# IMX385_EVB_revA.net
KiCad netlist of a schematic drawn in Altium Designer
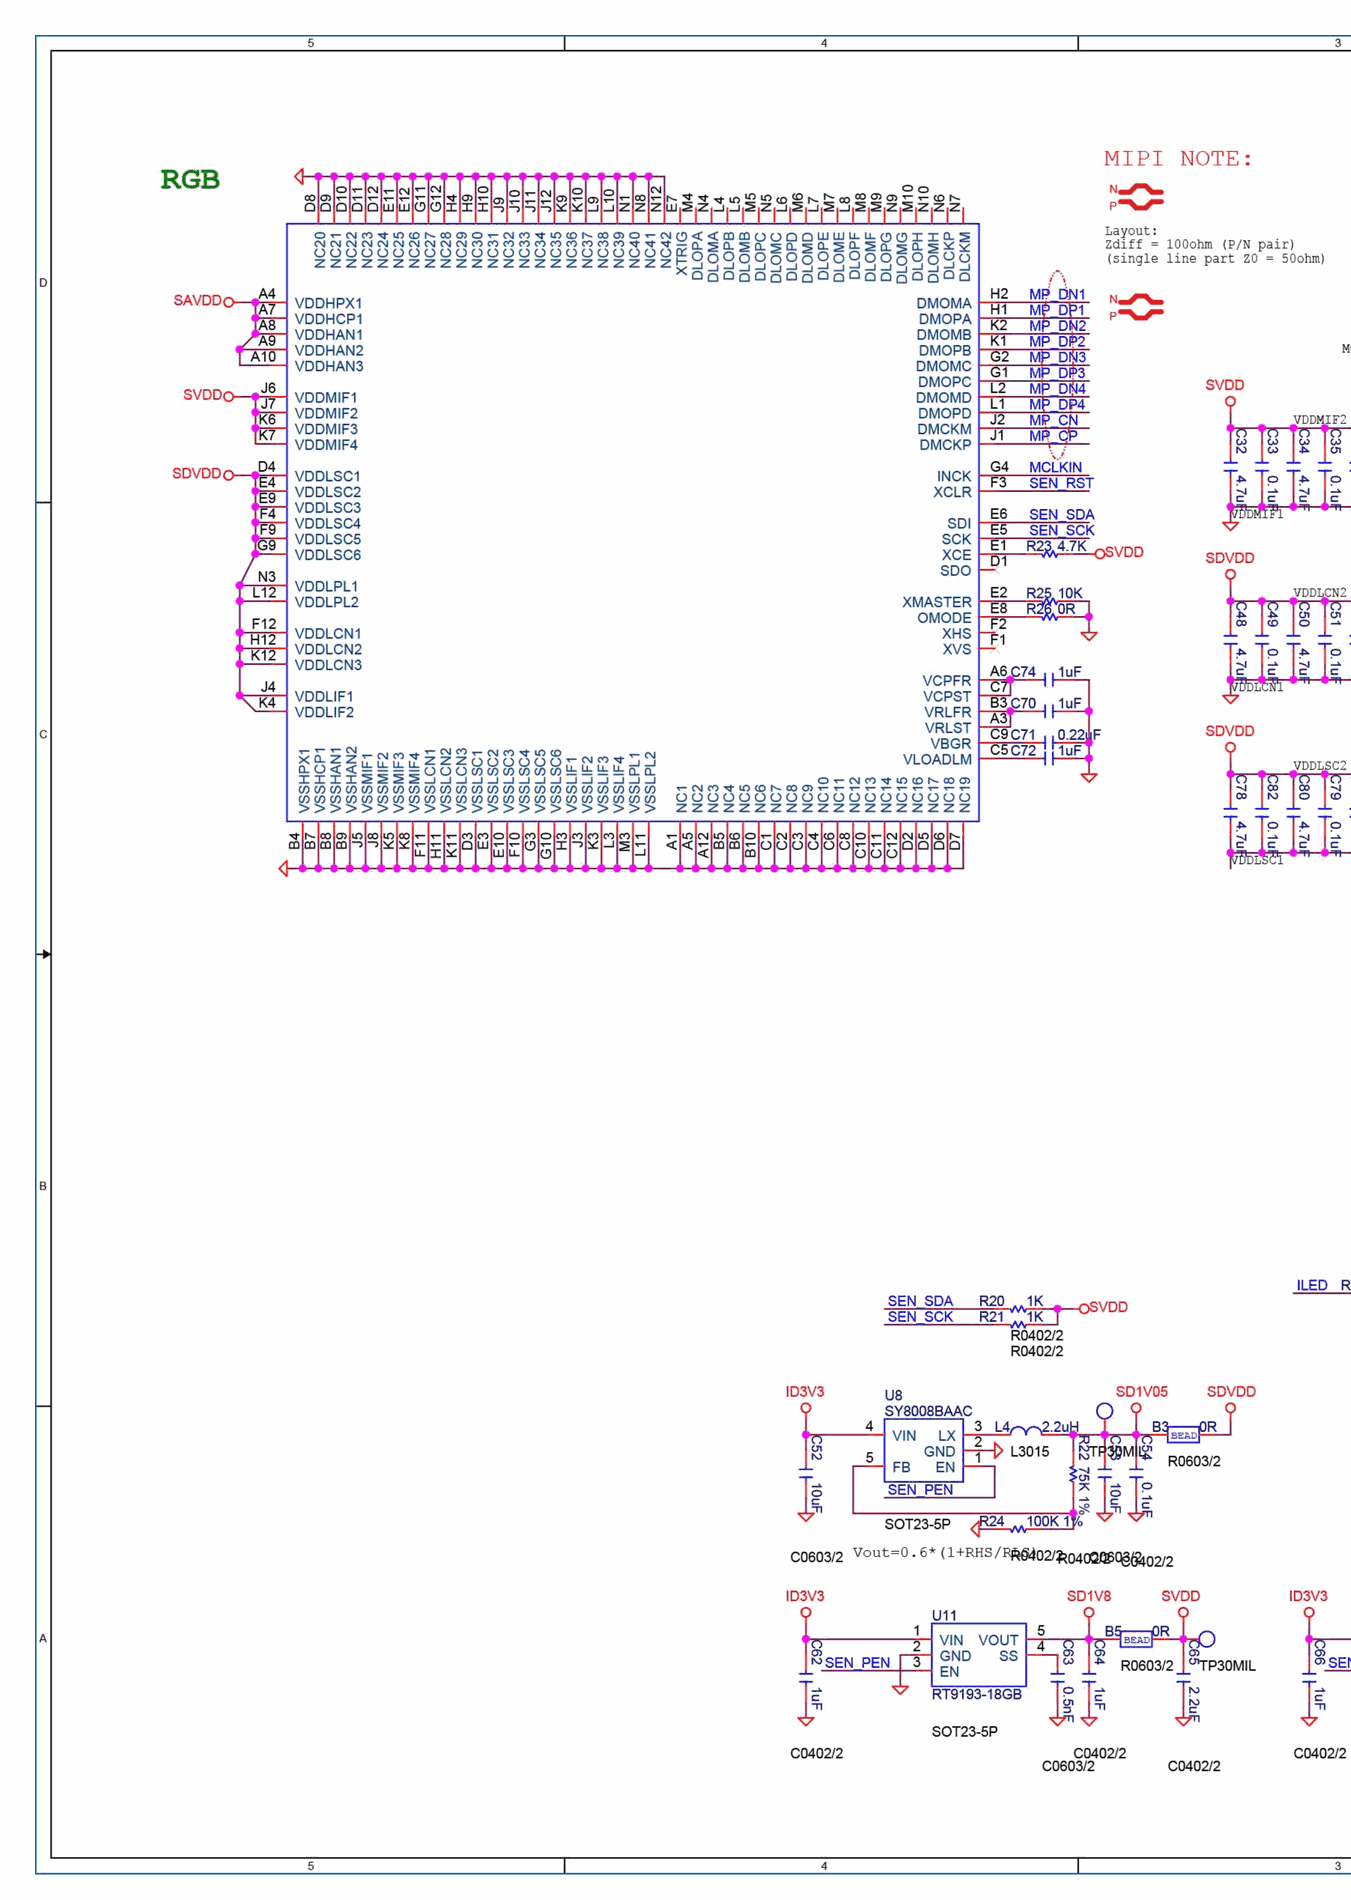
[diagram p0: IMX385_EVB_revA.SchDoc, top left]
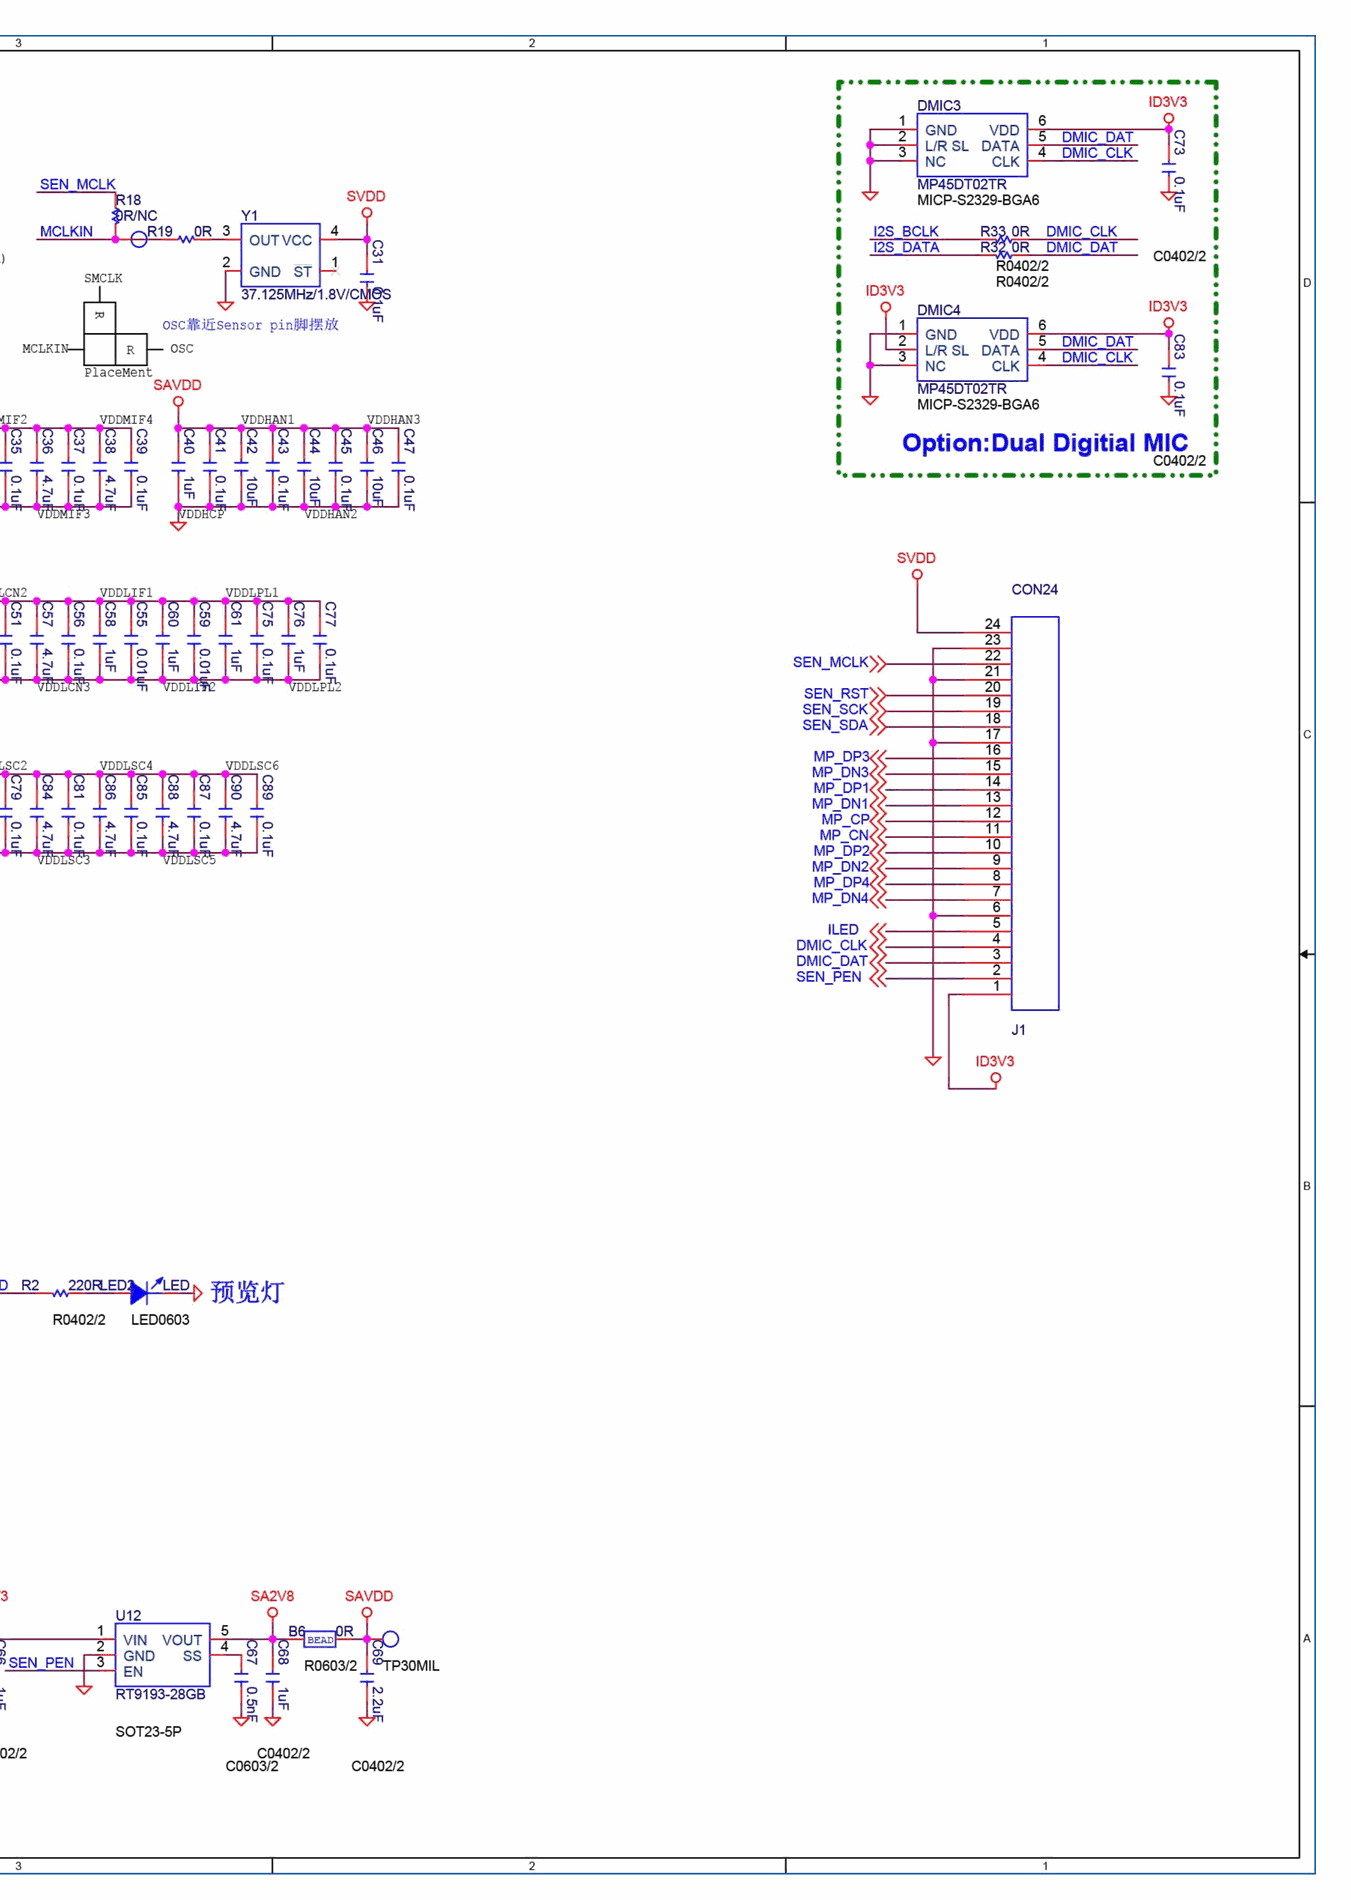
[diagram p1: IMX385_EVB_revA.SchDoc, top right]
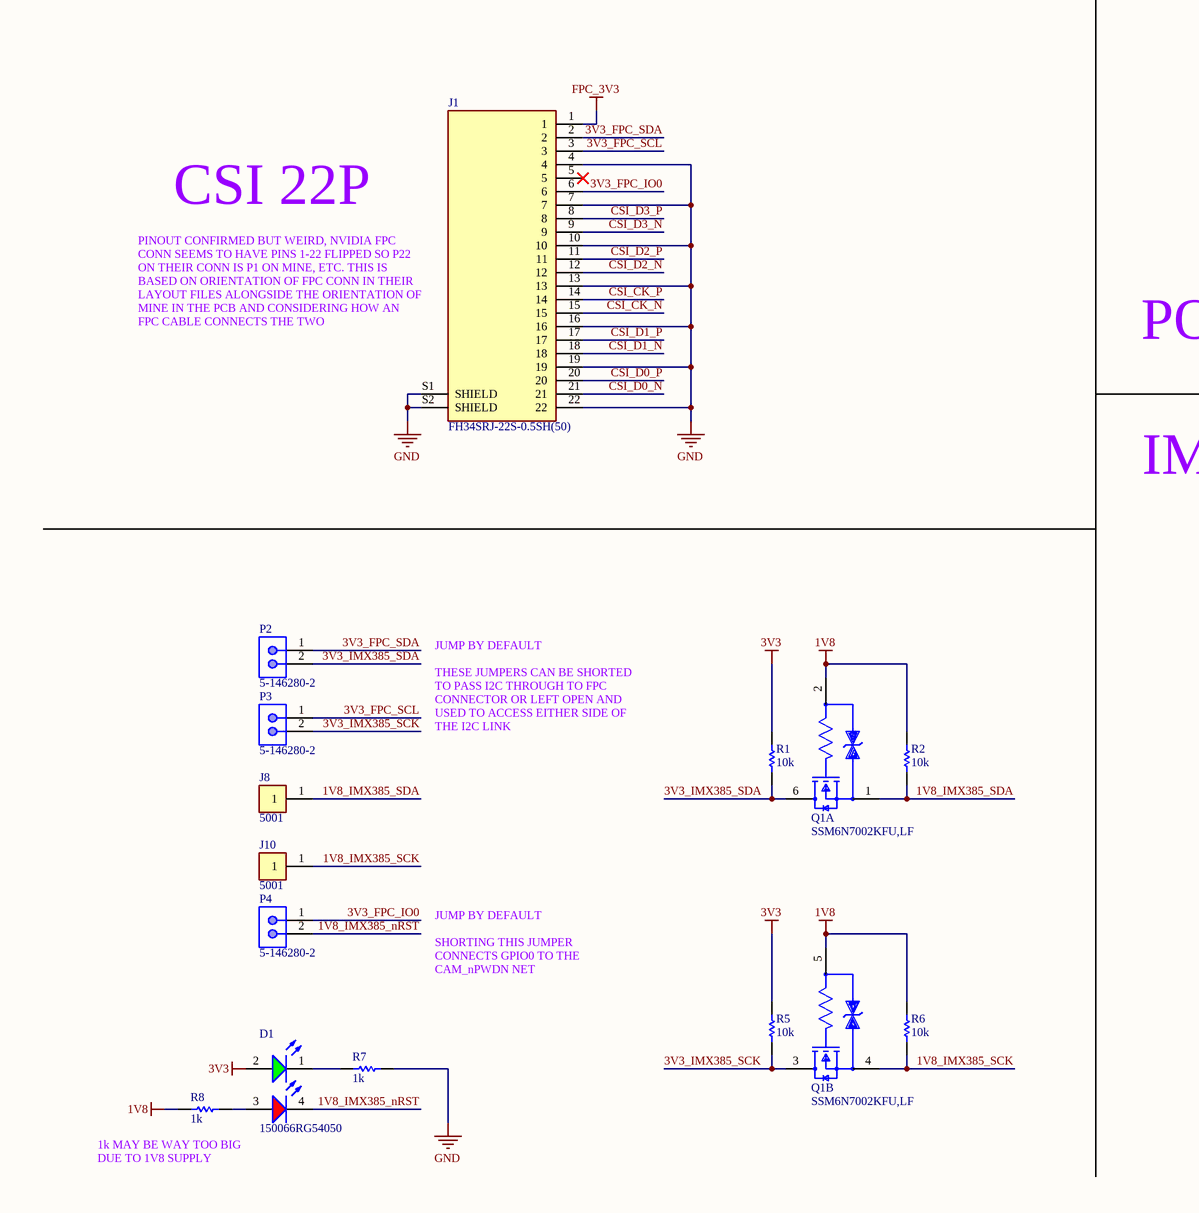
[diagram p2: IMX385_EVB_revA.SchDoc, bottom left]
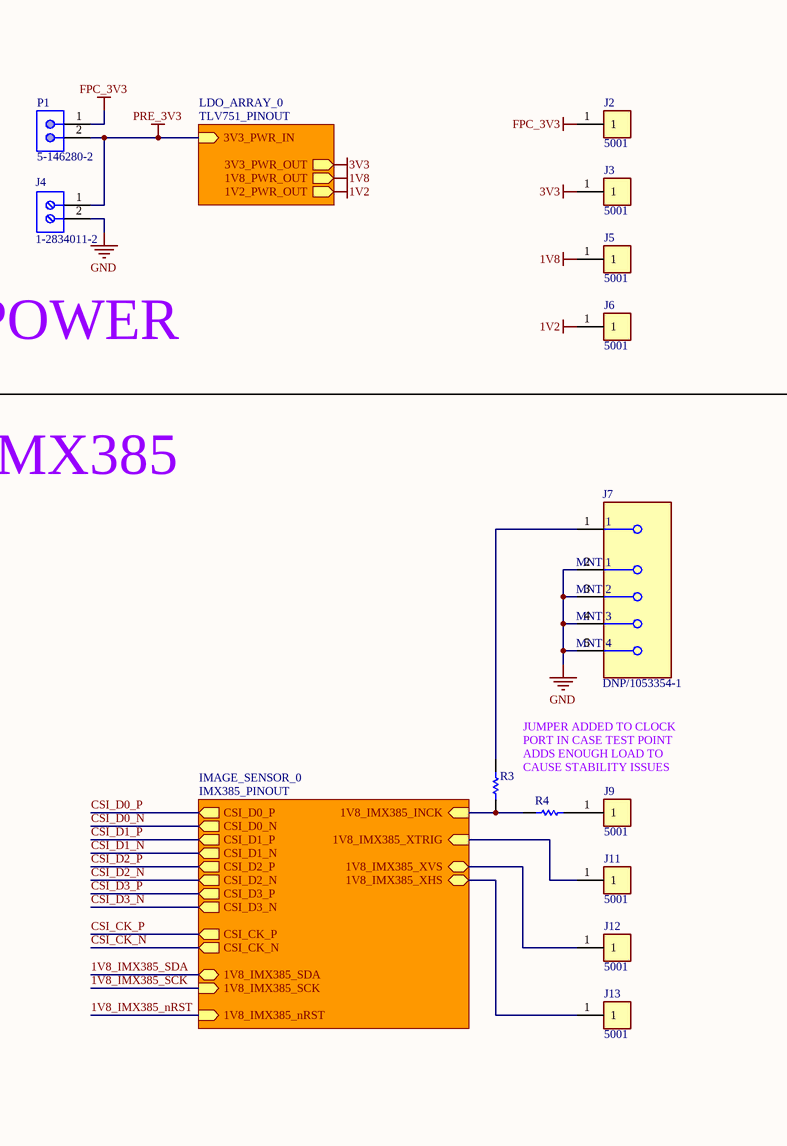
[diagram p3: IMX385_EVB_revA.SchDoc, bottom right]

(export (version "E")
  (design (tool "Eeschema 10.0.6"))
  (components
    (comp (ref "D1")
      (value "150066RG54050")
      (footprint "WL-SBCD_0606")
      (description "Led, Red/Grn, 180Mcd/230Mcd, 624Nm/525Nm Rohs Compliant: Yes")
      (fields (field (name "SOURCE") "rgled.SchLib"))
      (libsource (lib "Space Concordia") (part "CMP-004-00034-2"))
    )
    (comp (ref "J1")
      (value "FH34SRJ-22S-0.5SH(50)")
      (footprint "FH34SRJ-22S-0.5SH(50)-Footprint-1")
      (description "0.5Mm Pitch, 1.0Mm Height, Top And Bottom Contact, Back-Flip")
      (libsource (lib "Space Concordia") (part "FH34SRJ-22S-0.5SH(50)"))
    )
    (comp (ref "J2")
      (value "5001")
      (footprint "FP-5001-MFG")
      (description "PC TEST POINT MINIATURE BLACK")
      (libsource (lib "Altium Content Vault") (part "1e4615820a309e3ce90f9e6d957b7fa"))
    )
    (comp (ref "J3")
      (value "5001")
      (footprint "FP-5001-MFG")
      (description "PC TEST POINT MINIATURE BLACK")
      (libsource (lib "Altium Content Vault") (part "1e4615820a309e3ce90f9e6d957b7fa"))
    )
    (comp (ref "J4")
      (value "1-2834011-2")
      (footprint "1-2834011-2-Footprint-1")
      (description "Barrier Strip Terminal Block")
      (libsource (lib "Space Concordia") (part "1-2834011-2"))
    )
    (comp (ref "J5")
      (value "5001")
      (footprint "FP-5001-MFG")
      (description "PC TEST POINT MINIATURE BLACK")
      (libsource (lib "Altium Content Vault") (part "1e4615820a309e3ce90f9e6d957b7fa"))
    )
    (comp (ref "J6")
      (value "5001")
      (footprint "FP-5001-MFG")
      (description "PC TEST POINT MINIATURE BLACK")
      (libsource (lib "Altium Content Vault") (part "1e4615820a309e3ce90f9e6d957b7fa"))
    )
    (comp (ref "J7")
      (value "DNP/1053354-1")
      (footprint "FP-1053354-1-MFG")
      (description "CONN SMA JACK STR 50 OHM PCB")
      (libsource (lib "Altium Content Vault") (part "c65b8a639cdaef1819ea20b5466f8fa"))
    )
    (comp (ref "J8")
      (value "5001")
      (footprint "FP-5001-MFG")
      (description "PC TEST POINT MINIATURE BLACK")
      (libsource (lib "") (part "1e4615820a309e3ce90f9e6d957b7fa_1"))
    )
    (comp (ref "J9")
      (value "5001")
      (footprint "FP-5001-MFG")
      (description "PC TEST POINT MINIATURE BLACK")
      (libsource (lib "Altium Content Vault") (part "1e4615820a309e3ce90f9e6d957b7fa"))
    )
    (comp (ref "J10")
      (value "5001")
      (footprint "FP-5001-MFG")
      (description "PC TEST POINT MINIATURE BLACK")
      (libsource (lib "") (part "1e4615820a309e3ce90f9e6d957b7fa_1"))
    )
    (comp (ref "J11")
      (value "5001")
      (footprint "FP-5001-MFG")
      (description "PC TEST POINT MINIATURE BLACK")
      (libsource (lib "Altium Content Vault") (part "1e4615820a309e3ce90f9e6d957b7fa"))
    )
    (comp (ref "J12")
      (value "5001")
      (footprint "FP-5001-MFG")
      (description "PC TEST POINT MINIATURE BLACK")
      (libsource (lib "Altium Content Vault") (part "1e4615820a309e3ce90f9e6d957b7fa"))
    )
    (comp (ref "J13")
      (value "5001")
      (footprint "FP-5001-MFG")
      (description "PC TEST POINT MINIATURE BLACK")
      (libsource (lib "Altium Content Vault") (part "1e4615820a309e3ce90f9e6d957b7fa"))
    )
    (comp (ref "P1")
      (value "5-146280-2")
      (footprint "TECO-5-146280-2_V")
      (fields (field (name "MANUFACTURER") "TE Connectivity"))
      (libsource (lib "Altium Content Vault") (part "CN-1P-M-R2"))
    )
    (comp (ref "P2")
      (value "5-146280-2")
      (footprint "TECO-5-146280-2_V")
      (fields (field (name "MANUFACTURER") "TE Connectivity"))
      (libsource (lib "Altium Content Vault") (part "CN-1P-M-R2"))
    )
    (comp (ref "P3")
      (value "5-146280-2")
      (footprint "TECO-5-146280-2_V")
      (fields (field (name "MANUFACTURER") "TE Connectivity"))
      (libsource (lib "Altium Content Vault") (part "CN-1P-M-R2"))
    )
    (comp (ref "P4")
      (value "5-146280-2")
      (footprint "TECO-5-146280-2_V")
      (fields (field (name "MANUFACTURER") "TE Connectivity"))
      (libsource (lib "Altium Content Vault") (part "CN-1P-M-R2"))
    )
    (comp (ref "Q1")
      (value "SSM6N7002KFU,LF")
      (footprint "FP-SSOP6-P-0_65A-MFG")
      (description "MOSFET 2N-CH 60V 0.3A")
      (libsource (lib "Altium Content Vault") (part "088aa6ac103fdeebe0d1c52ece6b7b9"))
    )
    (comp (ref "R1")
      (value "10k")
      (footprint "R0603B")
      (description "Resistor")
      (libsource (lib "Space Concordia") (part "Resistor"))
    )
    (comp (ref "R2")
      (value "10k")
      (footprint "R0603B")
      (description "Resistor")
      (libsource (lib "Space Concordia") (part "Resistor"))
    )
    (comp (ref "R3")
      (value "DNP")
      (footprint "RESC1005X40X25ML05T05")
      (description "READ THE NAME")
      (libsource (lib "Space Concordia") (part "CMP-009-00206-2"))
    )
    (comp (ref "R4")
      (value "0402 JUMPER")
      (footprint "RESC1005X40X25ML05T05")
      (description "READ THE NAME")
      (libsource (lib "Space Concordia") (part "CMP-009-00206-2"))
    )
    (comp (ref "R5")
      (value "10k")
      (footprint "R0603B")
      (description "Resistor")
      (libsource (lib "Space Concordia") (part "Resistor"))
    )
    (comp (ref "R6")
      (value "10k")
      (footprint "R0603B")
      (description "Resistor")
      (libsource (lib "Space Concordia") (part "Resistor"))
    )
    (comp (ref "R7")
      (value "1k")
      (footprint "R0603B")
      (description "Resistor")
      (libsource (lib "Space Concordia") (part "Resistor"))
    )
    (comp (ref "R8")
      (value "1k")
      (footprint "R0603B")
      (description "Resistor")
      (libsource (lib "Space Concordia") (part "Resistor"))
    )
  )
  (nets
    (net (code "1") (name "/1V8_IMX385_INCK") (class "Default")
      (node (ref "R3") (pin "1") (pinfunction "1_1") (pintype "passive"))
      (node (ref "R4") (pin "1") (pinfunction "1_1") (pintype "passive"))
    )
    (net (code "2") (name "/1V8_IMX385_SCK") (class "Default")
      (node (ref "J10") (pin "1") (pinfunction "1_1") (pintype "passive"))
      (node (ref "Q1") (pin "4") (pinfunction "Source2_4") (pintype "passive"))
      (node (ref "R6") (pin "1") (pinfunction "1_1") (pintype "passive"))
    )
    (net (code "3") (name "/1V8_IMX385_SDA") (class "Default")
      (node (ref "J8") (pin "1") (pinfunction "1_1") (pintype "passive"))
      (node (ref "Q1") (pin "1") (pinfunction "Source1_1") (pintype "passive"))
      (node (ref "R2") (pin "1") (pinfunction "1_1") (pintype "passive"))
    )
    (net (code "4") (name "/1V8_IMX385_XHS") (class "Default")
      (node (ref "J13") (pin "1") (pinfunction "1_1") (pintype "passive"))
    )
    (net (code "5") (name "/1V8_IMX385_XTRIG") (class "Default")
      (node (ref "J11") (pin "1") (pinfunction "1_1") (pintype "passive"))
    )
    (net (code "6") (name "/1V8_IMX385_XVS") (class "Default")
      (node (ref "J12") (pin "1") (pinfunction "1_1") (pintype "passive"))
    )
    (net (code "7") (name "/1V8_IMX385_nRST") (class "Default")
      (node (ref "D1") (pin "4") (pinfunction "K_4") (pintype "passive"))
      (node (ref "P4") (pin "2") (pinfunction "2_2") (pintype "passive"))
    )
    (net (code "8") (name "/3V3_FPC_IO0") (class "Default")
      (node (ref "J1") (pin "6") (pinfunction "6_6") (pintype "passive"))
      (node (ref "P4") (pin "1") (pinfunction "1_1") (pintype "passive"))
    )
    (net (code "9") (name "/3V3_FPC_SCL") (class "Default")
      (node (ref "J1") (pin "3") (pinfunction "3_3") (pintype "passive"))
      (node (ref "P3") (pin "1") (pinfunction "1_1") (pintype "passive"))
    )
    (net (code "10") (name "/3V3_FPC_SDA") (class "Default")
      (node (ref "J1") (pin "2") (pinfunction "2_2") (pintype "passive"))
      (node (ref "P2") (pin "1") (pinfunction "1_1") (pintype "passive"))
    )
    (net (code "11") (name "/3V3_IMX385_SCK") (class "Default")
      (node (ref "P3") (pin "2") (pinfunction "2_2") (pintype "passive"))
      (node (ref "Q1") (pin "3") (pinfunction "Drain2_3") (pintype "passive"))
      (node (ref "R5") (pin "1") (pinfunction "1_1") (pintype "passive"))
    )
    (net (code "12") (name "/3V3_IMX385_SDA") (class "Default")
      (node (ref "P2") (pin "2") (pinfunction "2_2") (pintype "passive"))
      (node (ref "Q1") (pin "6") (pinfunction "Drain1_6") (pintype "passive"))
      (node (ref "R1") (pin "1") (pinfunction "1_1") (pintype "passive"))
    )
    (net (code "13") (name "/CSI_CK_N") (class "Default")
      (node (ref "J1") (pin "15") (pinfunction "15_15") (pintype "passive"))
    )
    (net (code "14") (name "/CSI_CK_P") (class "Default")
      (node (ref "J1") (pin "14") (pinfunction "14_14") (pintype "passive"))
    )
    (net (code "15") (name "/CSI_D0_N") (class "Default")
      (node (ref "J1") (pin "21") (pinfunction "21_21") (pintype "passive"))
    )
    (net (code "16") (name "/CSI_D0_P") (class "Default")
      (node (ref "J1") (pin "20") (pinfunction "20_20") (pintype "passive"))
    )
    (net (code "17") (name "/CSI_D1_N") (class "Default")
      (node (ref "J1") (pin "18") (pinfunction "18_18") (pintype "passive"))
    )
    (net (code "18") (name "/CSI_D1_P") (class "Default")
      (node (ref "J1") (pin "17") (pinfunction "17_17") (pintype "passive"))
    )
    (net (code "19") (name "/CSI_D2_N") (class "Default")
      (node (ref "J1") (pin "12") (pinfunction "12_12") (pintype "passive"))
    )
    (net (code "20") (name "/CSI_D2_P") (class "Default")
      (node (ref "J1") (pin "11") (pinfunction "11_11") (pintype "passive"))
    )
    (net (code "21") (name "/CSI_D3_N") (class "Default")
      (node (ref "J1") (pin "9") (pinfunction "9_9") (pintype "passive"))
    )
    (net (code "22") (name "/CSI_D3_P") (class "Default")
      (node (ref "J1") (pin "8") (pinfunction "8_8") (pintype "passive"))
    )
    (net (code "23") (name "1V2") (class "Default")
      (node (ref "J6") (pin "1") (pinfunction "1_1") (pintype "passive"))
    )
    (net (code "24") (name "1V8") (class "Default")
      (node (ref "J5") (pin "1") (pinfunction "1_1") (pintype "passive"))
      (node (ref "Q1") (pin "2") (pinfunction "Gate1_2") (pintype "passive"))
      (node (ref "Q1") (pin "5") (pinfunction "Gate2_5") (pintype "passive"))
      (node (ref "R2") (pin "2") (pinfunction "2_2") (pintype "passive"))
      (node (ref "R6") (pin "2") (pinfunction "2_2") (pintype "passive"))
      (node (ref "R8") (pin "2") (pinfunction "2_2") (pintype "passive"))
    )
    (net (code "25") (name "3V3") (class "Default")
      (node (ref "D1") (pin "2") (pinfunction "A_2") (pintype "passive"))
      (node (ref "J3") (pin "1") (pinfunction "1_1") (pintype "passive"))
      (node (ref "R1") (pin "2") (pinfunction "2_2") (pintype "passive"))
      (node (ref "R5") (pin "2") (pinfunction "2_2") (pintype "passive"))
    )
    (net (code "26") (name "FPC_3V3") (class "Default")
      (node (ref "J1") (pin "1") (pinfunction "1_1") (pintype "passive"))
      (node (ref "J2") (pin "1") (pinfunction "1_1") (pintype "passive"))
      (node (ref "P1") (pin "1") (pinfunction "1_1") (pintype "passive"))
    )
    (net (code "27") (name "GND") (class "Default")
      (node (ref "J1") (pin "10") (pinfunction "10_10") (pintype "passive"))
      (node (ref "J1") (pin "13") (pinfunction "13_13") (pintype "passive"))
      (node (ref "J1") (pin "16") (pinfunction "16_16") (pintype "passive"))
      (node (ref "J1") (pin "19") (pinfunction "19_19") (pintype "passive"))
      (node (ref "J1") (pin "22") (pinfunction "22_22") (pintype "passive"))
      (node (ref "J1") (pin "4") (pinfunction "4_4") (pintype "passive"))
      (node (ref "J1") (pin "7") (pinfunction "7_7") (pintype "passive"))
      (node (ref "J1") (pin "S1") (pinfunction "SHIELD_S1") (pintype "passive"))
      (node (ref "J1") (pin "S2") (pinfunction "SHIELD_S2") (pintype "passive"))
      (node (ref "J4") (pin "2") (pinfunction "2_2") (pintype "passive"))
      (node (ref "J7") (pin "2") (pinfunction "MNT_1_2") (pintype "passive"))
      (node (ref "J7") (pin "3") (pinfunction "MNT_2_3") (pintype "passive"))
      (node (ref "J7") (pin "4") (pinfunction "MNT_3_4") (pintype "passive"))
      (node (ref "J7") (pin "5") (pinfunction "MNT_4_5") (pintype "passive"))
      (node (ref "R7") (pin "1") (pinfunction "1_1") (pintype "passive"))
    )
    (net (code "28") (name "Net-(D1-A-Pad3)") (class "Default")
      (node (ref "D1") (pin "3") (pinfunction "A_3") (pintype "passive"))
      (node (ref "R8") (pin "1") (pinfunction "1_1") (pintype "passive"))
    )
    (net (code "29") (name "Net-(D1-K-Pad1)") (class "Default")
      (node (ref "D1") (pin "1") (pinfunction "K_1") (pintype "passive"))
      (node (ref "R7") (pin "2") (pinfunction "2_2") (pintype "passive"))
    )
    (net (code "30") (name "Net-(J7-Pad1)") (class "Default")
      (node (ref "J7") (pin "1") (pinfunction "1_1") (pintype "passive"))
      (node (ref "R3") (pin "2") (pinfunction "2_2") (pintype "passive"))
    )
    (net (code "31") (name "Net-(J9-Pad1)") (class "Default")
      (node (ref "J9") (pin "1") (pinfunction "1_1") (pintype "passive"))
      (node (ref "R4") (pin "2") (pinfunction "2_2") (pintype "passive"))
    )
    (net (code "32") (name "PRE_3V3") (class "Default")
      (node (ref "J4") (pin "1") (pinfunction "1_1") (pintype "passive"))
      (node (ref "P1") (pin "2") (pinfunction "2_2") (pintype "passive"))
    )
    (net (code "33") (name "unconnected-(J1-Pad5)") (class "Default")
      (node (ref "J1") (pin "5") (pinfunction "5_5") (pintype "passive+no_connect"))
    )
  )
)
